# ZYNQ_MIOBank_501.net
KiCad netlist of a schematic drawn in Altium Designer
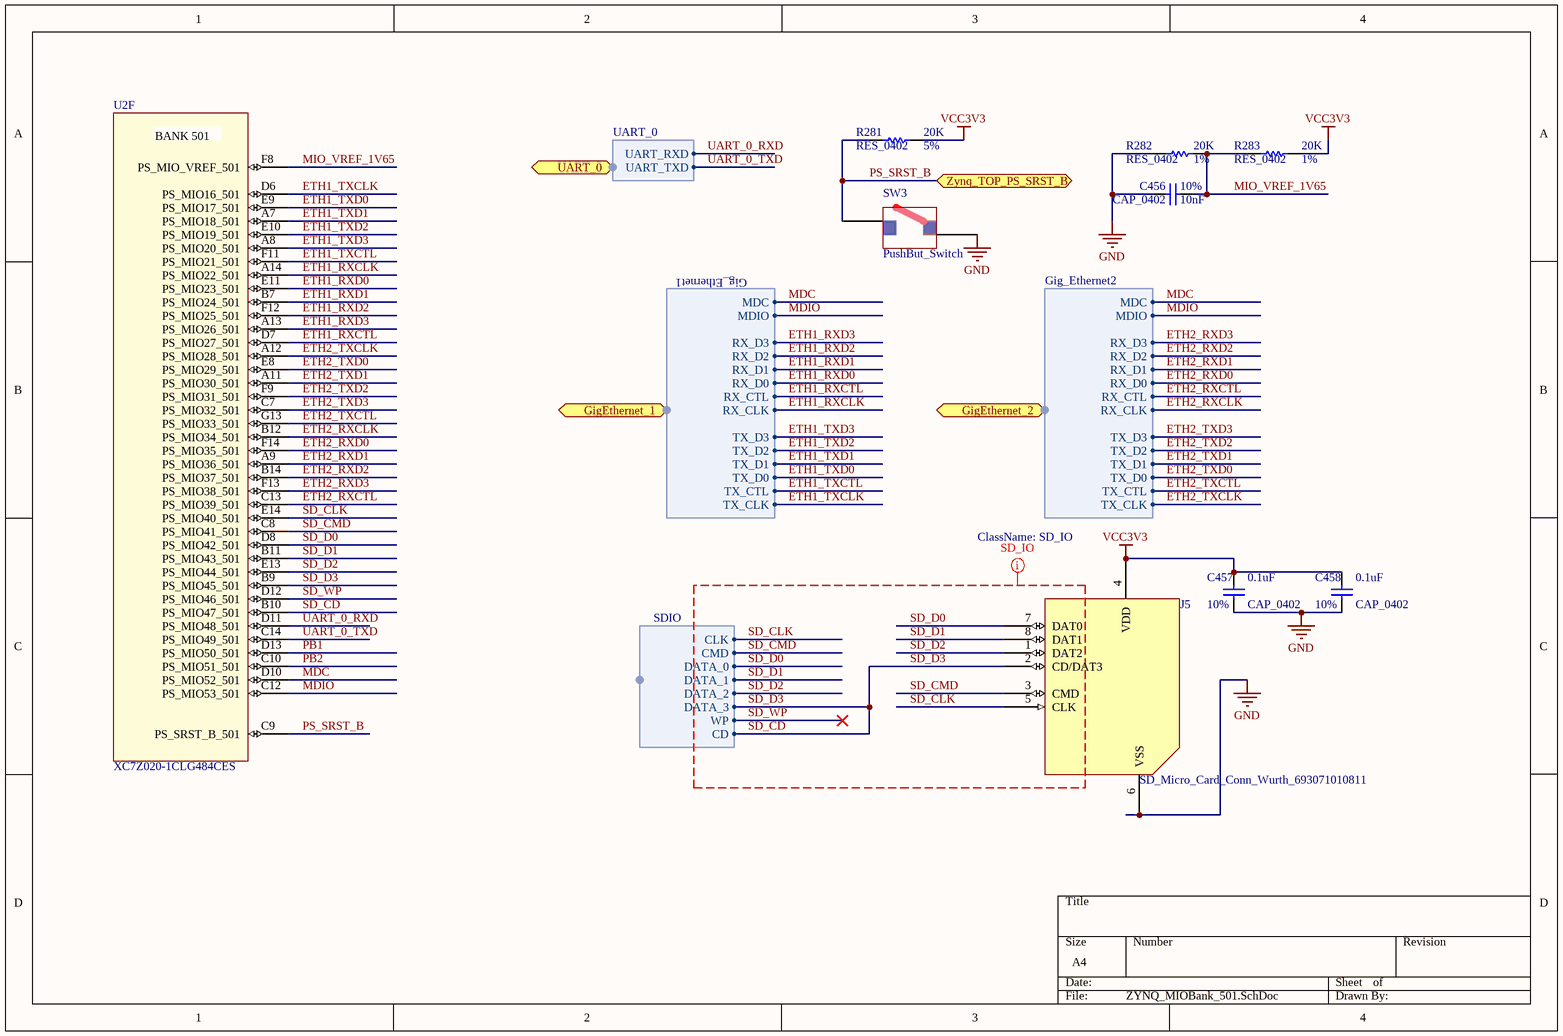
[diagram p0: ZYNQ_MIOBank_501.SchDoc]

(export (version "E")
  (design (tool "Eeschema 10.0.6"))
  (components
    (comp (ref "C456")
      (value "CAP_0402")
      (footprint "CAPC0402(1005)60_N:CAPC0402(1005)60_N")
      (description "10000pF, ceramic, 10% 6.3V X5R, 0402")
      (fields
        (field (name "ALTIUM_VALUE") "10nF")
        (field (name "TOLERANCE") "10%")
        (field (name "PART NUMBER") "GRM155R60J103KA01D")
        (field (name "MANUFACTURER") "Murata Electronics North America")
      )
      (libsource (lib "COMRAD_Database") (part "CAP_0402"))
    )
    (comp (ref "C457")
      (value "CAP_0402")
      (footprint "CAPC0402(1005)60_N:CAPC0402(1005)60_N")
      (description "0.1uf, ceramic, 10%, 6.3V, X5R, 0402")
      (fields
        (field (name "ALTIUM_VALUE") "0.1uF")
        (field (name "TOLERANCE") "10%")
        (field (name "PART NUMBER") "C1005X5R0J104K")
        (field (name "MANUFACTURER") "TDK Corporation")
      )
      (libsource (lib "COMRAD_Database") (part "CAP_0402"))
    )
    (comp (ref "C458")
      (value "CAP_0402")
      (footprint "CAPC0402(1005)60_N:CAPC0402(1005)60_N")
      (description "0.1uf, ceramic, 10%, 6.3V, X5R, 0402")
      (fields
        (field (name "ALTIUM_VALUE") "0.1uF")
        (field (name "TOLERANCE") "10%")
        (field (name "PART NUMBER") "C1005X5R0J104K")
        (field (name "MANUFACTURER") "TDK Corporation")
      )
      (libsource (lib "COMRAD_Database") (part "CAP_0402"))
    )
    (comp (ref "J5")
      (value "SD_Micro_Card_Conn_Wurth_693071010811")
      (footprint "SD_Micro_Card_Conn_Wurth_693071010811")
      (description "CONN MICRO SD 8 POS SMD")
      (fields
        (field (name "PART NUMBER") "\"693071010811\"")
        (field (name "MANUFACTURER") "Wurth Electronics Inc")
      )
      (libsource (lib "COMRAD_Database") (part "SD_Micro_Card_Conn_Wurth_693071010811_schm"))
    )
    (comp (ref "R281")
      (value "RES_0402")
      (footprint "RESC0402(1005)_N:RESC0402(1005)_N")
      (description "20K ohm, 5%, 1/16W, 0402")
      (fields
        (field (name "ALTIUM_VALUE") "20K")
        (field (name "TOLERANCE") "5%")
        (field (name "PART NUMBER") "ERJ-2GEJ203X")
        (field (name "MANUFACTURER") "Panasonic - ECG")
      )
      (libsource (lib "COMRAD_Database") (part "RES_0402"))
    )
    (comp (ref "R282")
      (value "RES_0402")
      (footprint "RESC0402(1005)_N:RESC0402(1005)_N")
      (description "RES 20.0K OHM 1/10W 1% 0402 SMD")
      (fields
        (field (name "ALTIUM_VALUE") "20K")
        (field (name "TOLERANCE") "1%")
        (field (name "PART NUMBER") "ERJ-2RKF2002X")
        (field (name "MANUFACTURER") "Panasonic Electronic Components")
      )
      (libsource (lib "COMRAD_Database") (part "RES_0402"))
    )
    (comp (ref "R283")
      (value "RES_0402")
      (footprint "RESC0402(1005)_N:RESC0402(1005)_N")
      (description "RES 20.0K OHM 1/10W 1% 0402 SMD")
      (fields
        (field (name "ALTIUM_VALUE") "20K")
        (field (name "TOLERANCE") "1%")
        (field (name "PART NUMBER") "ERJ-2RKF2002X")
        (field (name "MANUFACTURER") "Panasonic Electronic Components")
      )
      (libsource (lib "COMRAD_Database") (part "RES_0402"))
    )
    (comp (ref "SW3")
      (value "PushBut_Switch")
      (footprint "PushButtonSwitch_CnK_1.14002.1110000")
      (description "SWITCH PUSH SPST-NO 0.1A 35V")
      (fields (field (name "PART NUMBER") "1.14002.1110000") (field (name "MANUFACTURER") "C&K Components"))
      (libsource (lib "COMRAD_Database") (part "PushBut_Switch"))
    )
    (comp (ref "U2")
      (value "XC7Z020-1CLG484CES")
      (footprint "ZYNQ_xc7z020clg484pkg_BGA-484")
      (description "XC7Z020-1CLG484CES, Zynq-7000 All Programmable SoC")
      (fields (field (name "MANUFACTURER") "Xilinx"))
      (libsource (lib "COMRAD_Database") (part "ZYNQ_XC7Z020CLG484PKG"))
    )
  )
  (nets
    (net (code "4") (name "/ETH1_RXCLK") (class "Default")
      (node (ref "U2") (pin "A14") (pinfunction "PS_MIO22_501_A14") (pintype "bidirectional"))
    )
    (net (code "5") (name "/ETH1_RXCTL") (class "Default")
      (node (ref "U2") (pin "D7") (pinfunction "PS_MIO27_501_D7") (pintype "bidirectional"))
    )
    (net (code "6") (name "/ETH1_RXD0") (class "Default")
      (node (ref "U2") (pin "E11") (pinfunction "PS_MIO23_501_E11") (pintype "bidirectional"))
    )
    (net (code "7") (name "/ETH1_RXD1") (class "Default")
      (node (ref "U2") (pin "B7") (pinfunction "PS_MIO24_501_B7") (pintype "bidirectional"))
    )
    (net (code "8") (name "/ETH1_RXD2") (class "Default")
      (node (ref "U2") (pin "F12") (pinfunction "PS_MIO25_501_F12") (pintype "bidirectional"))
    )
    (net (code "9") (name "/ETH1_RXD3") (class "Default")
      (node (ref "U2") (pin "A13") (pinfunction "PS_MIO26_501_A13") (pintype "bidirectional"))
    )
    (net (code "10") (name "/ETH1_TXCLK") (class "Default")
      (node (ref "U2") (pin "D6") (pinfunction "PS_MIO16_501_D6") (pintype "bidirectional"))
    )
    (net (code "11") (name "/ETH1_TXCTL") (class "Default")
      (node (ref "U2") (pin "F11") (pinfunction "PS_MIO21_501_F11") (pintype "bidirectional"))
    )
    (net (code "12") (name "/ETH1_TXD0") (class "Default")
      (node (ref "U2") (pin "E9") (pinfunction "PS_MIO17_501_E9") (pintype "bidirectional"))
    )
    (net (code "13") (name "/ETH1_TXD1") (class "Default")
      (node (ref "U2") (pin "A7") (pinfunction "PS_MIO18_501_A7") (pintype "bidirectional"))
    )
    (net (code "14") (name "/ETH1_TXD2") (class "Default")
      (node (ref "U2") (pin "E10") (pinfunction "PS_MIO19_501_E10") (pintype "bidirectional"))
    )
    (net (code "15") (name "/ETH1_TXD3") (class "Default")
      (node (ref "U2") (pin "A8") (pinfunction "PS_MIO20_501_A8") (pintype "bidirectional"))
    )
    (net (code "16") (name "/ETH2_RXCLK") (class "Default")
      (node (ref "U2") (pin "B12") (pinfunction "PS_MIO34_501_B12") (pintype "bidirectional"))
    )
    (net (code "17") (name "/ETH2_RXCTL") (class "Default")
      (node (ref "U2") (pin "C13") (pinfunction "PS_MIO39_501_C13") (pintype "bidirectional"))
    )
    (net (code "18") (name "/ETH2_RXD0") (class "Default")
      (node (ref "U2") (pin "F14") (pinfunction "PS_MIO35_501_F14") (pintype "bidirectional"))
    )
    (net (code "19") (name "/ETH2_RXD1") (class "Default")
      (node (ref "U2") (pin "A9") (pinfunction "PS_MIO36_501_A9") (pintype "bidirectional"))
    )
    (net (code "20") (name "/ETH2_RXD2") (class "Default")
      (node (ref "U2") (pin "B14") (pinfunction "PS_MIO37_501_B14") (pintype "bidirectional"))
    )
    (net (code "21") (name "/ETH2_RXD3") (class "Default")
      (node (ref "U2") (pin "F13") (pinfunction "PS_MIO38_501_F13") (pintype "bidirectional"))
    )
    (net (code "22") (name "/ETH2_TXCLK") (class "Default")
      (node (ref "U2") (pin "A12") (pinfunction "PS_MIO28_501_A12") (pintype "bidirectional"))
    )
    (net (code "23") (name "/ETH2_TXCTL") (class "Default")
      (node (ref "U2") (pin "G13") (pinfunction "PS_MIO33_501_G13") (pintype "bidirectional"))
    )
    (net (code "24") (name "/ETH2_TXD0") (class "Default")
      (node (ref "U2") (pin "E8") (pinfunction "PS_MIO29_501_E8") (pintype "bidirectional"))
    )
    (net (code "25") (name "/ETH2_TXD1") (class "Default")
      (node (ref "U2") (pin "A11") (pinfunction "PS_MIO30_501_A11") (pintype "bidirectional"))
    )
    (net (code "26") (name "/ETH2_TXD2") (class "Default")
      (node (ref "U2") (pin "F9") (pinfunction "PS_MIO31_501_F9") (pintype "bidirectional"))
    )
    (net (code "27") (name "/ETH2_TXD3") (class "Default")
      (node (ref "U2") (pin "C7") (pinfunction "PS_MIO32_501_C7") (pintype "bidirectional"))
    )
    (net (code "28") (name "/MDC") (class "Default")
      (node (ref "U2") (pin "D10") (pinfunction "PS_MIO52_501_D10") (pintype "bidirectional"))
    )
    (net (code "29") (name "/MDIO") (class "Default")
      (node (ref "U2") (pin "C12") (pinfunction "PS_MIO53_501_C12") (pintype "bidirectional"))
    )
    (net (code "30") (name "/MIO_VREF_1V65") (class "Default")
      (node (ref "C456") (pin "1") (pinfunction "1_1") (pintype "passive"))
      (node (ref "R282") (pin "2") (pinfunction "2_2") (pintype "passive"))
      (node (ref "R283") (pin "1") (pinfunction "1_1") (pintype "passive"))
      (node (ref "U2") (pin "F8") (pinfunction "PS_MIO_VREF_501_F8") (pintype "bidirectional"))
    )
    (net (code "31") (name "/PB1") (class "Default")
      (node (ref "U2") (pin "D13") (pinfunction "PS_MIO50_501_D13") (pintype "bidirectional"))
    )
    (net (code "32") (name "/PB2") (class "Default")
      (node (ref "U2") (pin "C10") (pinfunction "PS_MIO51_501_C10") (pintype "bidirectional"))
    )
    (net (code "33") (name "/PS_SRST_B") (class "Default")
      (node (ref "R281") (pin "1") (pinfunction "1_1") (pintype "passive"))
      (node (ref "SW3") (pin "3") (pintype "passive"))
      (node (ref "U2") (pin "C9") (pinfunction "PS_SRST_B_501_C9") (pintype "bidirectional"))
    )
    (net (code "34") (name "/SD_CD") (class "Default")
      (node (ref "J5") (pin "2") (pinfunction "CD/DAT3_2") (pintype "bidirectional"))
      (node (ref "U2") (pin "B10") (pinfunction "PS_MIO47_501_B10") (pintype "bidirectional"))
      (node (ref "U2") (pin "B9") (pinfunction "PS_MIO45_501_B9") (pintype "bidirectional"))
    )
    (net (code "35") (name "/SD_CLK") (class "Default")
      (node (ref "J5") (pin "5") (pinfunction "CLK_5") (pintype "input"))
      (node (ref "U2") (pin "E14") (pinfunction "PS_MIO40_501_E14") (pintype "bidirectional"))
    )
    (net (code "36") (name "/SD_CMD") (class "Default")
      (node (ref "J5") (pin "3") (pinfunction "CMD_3") (pintype "bidirectional"))
      (node (ref "U2") (pin "C8") (pinfunction "PS_MIO41_501_C8") (pintype "bidirectional"))
    )
    (net (code "37") (name "/SD_D0") (class "Default")
      (node (ref "J5") (pin "7") (pinfunction "DAT0_7") (pintype "bidirectional"))
      (node (ref "U2") (pin "D8") (pinfunction "PS_MIO42_501_D8") (pintype "bidirectional"))
    )
    (net (code "38") (name "/SD_D1") (class "Default")
      (node (ref "J5") (pin "8") (pinfunction "DAT1_8") (pintype "bidirectional"))
      (node (ref "U2") (pin "B11") (pinfunction "PS_MIO43_501_B11") (pintype "bidirectional"))
    )
    (net (code "39") (name "/SD_D2") (class "Default")
      (node (ref "J5") (pin "1") (pinfunction "DAT2_1") (pintype "bidirectional"))
      (node (ref "U2") (pin "E13") (pinfunction "PS_MIO44_501_E13") (pintype "bidirectional"))
    )
    (net (code "40") (name "/SD_WP") (class "Default")
      (node (ref "U2") (pin "D12") (pinfunction "PS_MIO46_501_D12") (pintype "bidirectional+no_connect"))
    )
    (net (code "41") (name "/UART_0_RXD") (class "Default")
      (node (ref "U2") (pin "D11") (pinfunction "PS_MIO48_501_D11") (pintype "bidirectional"))
    )
    (net (code "42") (name "/UART_0_TXD") (class "Default")
      (node (ref "U2") (pin "C14") (pinfunction "PS_MIO49_501_C14") (pintype "bidirectional"))
    )
    (net (code "46") (name "GND") (class "Default")
      (node (ref "C456") (pin "2") (pinfunction "2_2") (pintype "passive"))
      (node (ref "C457") (pin "2") (pinfunction "2_2") (pintype "passive"))
      (node (ref "C458") (pin "2") (pinfunction "2_2") (pintype "passive"))
      (node (ref "J5") (pin "6") (pinfunction "VSS_6") (pintype "power_in"))
      (node (ref "R282") (pin "1") (pinfunction "1_1") (pintype "passive"))
      (node (ref "SW3") (pin "4") (pintype "passive"))
    )
    (net (code "47") (name "VCC3V3") (class "Default")
      (node (ref "C457") (pin "1") (pinfunction "1_1") (pintype "passive"))
      (node (ref "C458") (pin "1") (pinfunction "1_1") (pintype "passive"))
      (node (ref "J5") (pin "4") (pinfunction "VDD_4") (pintype "power_in"))
      (node (ref "R281") (pin "2") (pinfunction "2_2") (pintype "passive"))
      (node (ref "R283") (pin "2") (pinfunction "2_2") (pintype "passive"))
    )
  )
)
